# A.net
KiCad netlist of a schematic drawn in EAGLE
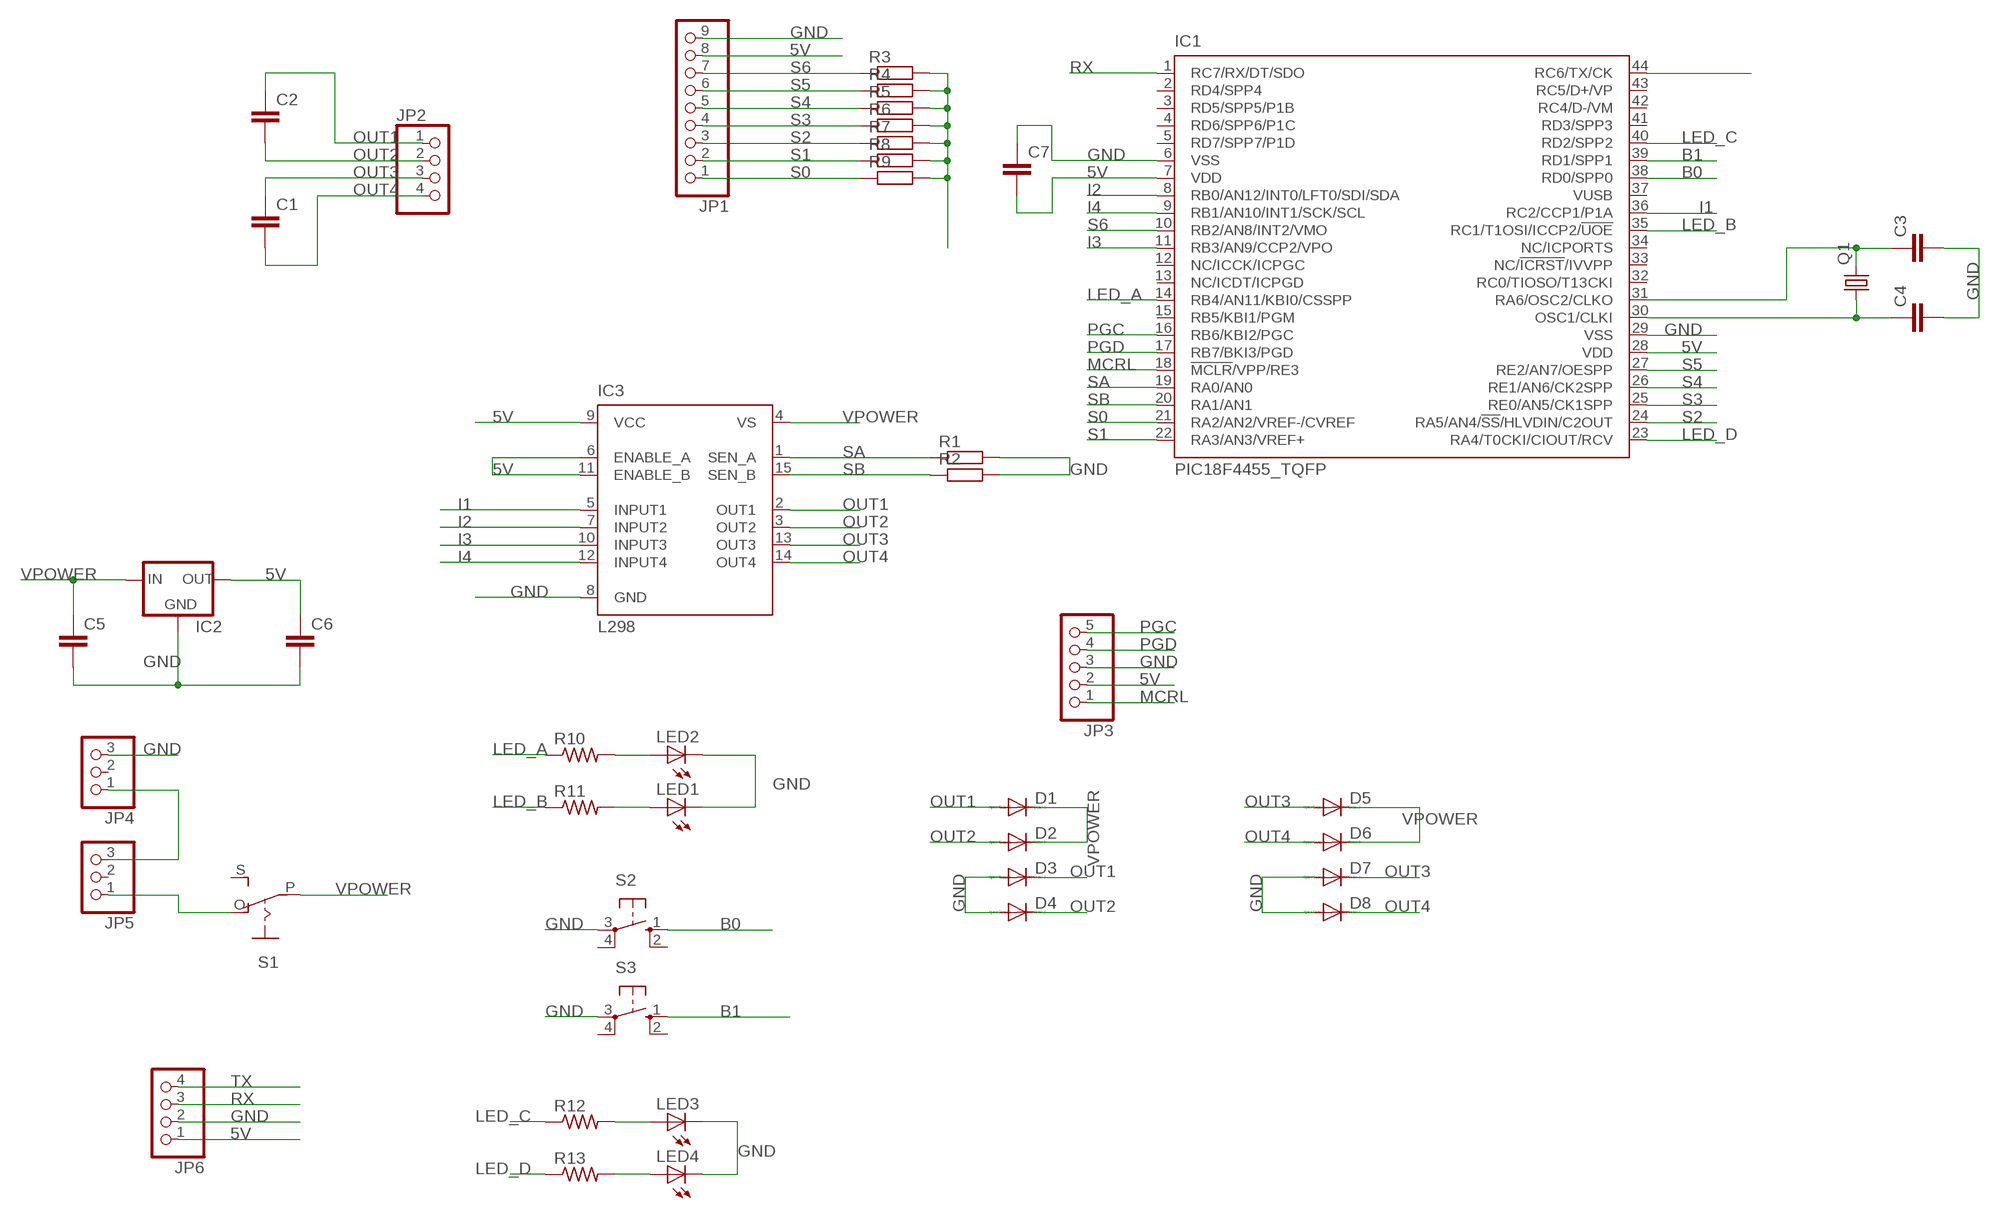
[diagram p0: schematic, sheet 1]

(export (version "E")
  (design (tool "Eeschema 10.0.6"))
  (components
    (comp (ref "C1")
      (value "C2,5-3")
      (footprint "eagle-import:C2.5-3")
      (libsource (lib "eagle-import") (part "C2,5-3"))
    )
    (comp (ref "C2")
      (value "C2,5-3")
      (footprint "eagle-import:C2.5-3")
      (libsource (lib "eagle-import") (part "C2,5-3"))
    )
    (comp (ref "C3")
      (value "C2,5-3")
      (footprint "eagle-import:C2.5-3")
      (libsource (lib "eagle-import") (part "C2,5-3"))
    )
    (comp (ref "C4")
      (value "C2,5-3")
      (footprint "eagle-import:C2.5-3")
      (libsource (lib "eagle-import") (part "C2,5-3"))
    )
    (comp (ref "C5")
      (value "C2,5-3")
      (footprint "eagle-import:C2.5-3")
      (libsource (lib "eagle-import") (part "C2,5-3"))
    )
    (comp (ref "C6")
      (value "C2,5-3")
      (footprint "eagle-import:C2.5-3")
      (libsource (lib "eagle-import") (part "C2,5-3"))
    )
    (comp (ref "C7")
      (value "C2,5-3")
      (footprint "eagle-import:C2.5-3")
      (libsource (lib "eagle-import") (part "C2,5-3"))
    )
    (comp (ref "D1")
      (value "DIODE-DO214AC")
      (footprint "eagle-import:DO214AC")
      (libsource (lib "eagle-import") (part "DIODE-DO214AC"))
    )
    (comp (ref "D2")
      (value "DIODE-DO214AC")
      (footprint "eagle-import:DO214AC")
      (libsource (lib "eagle-import") (part "DIODE-DO214AC"))
    )
    (comp (ref "D3")
      (value "DIODE-DO214AC")
      (footprint "eagle-import:DO214AC")
      (libsource (lib "eagle-import") (part "DIODE-DO214AC"))
    )
    (comp (ref "D4")
      (value "DIODE-DO214AC")
      (footprint "eagle-import:DO214AC")
      (libsource (lib "eagle-import") (part "DIODE-DO214AC"))
    )
    (comp (ref "D5")
      (value "DIODE-DO214AC")
      (footprint "eagle-import:DO214AC")
      (libsource (lib "eagle-import") (part "DIODE-DO214AC"))
    )
    (comp (ref "D6")
      (value "DIODE-DO214AC")
      (footprint "eagle-import:DO214AC")
      (libsource (lib "eagle-import") (part "DIODE-DO214AC"))
    )
    (comp (ref "D7")
      (value "DIODE-DO214AC")
      (footprint "eagle-import:DO214AC")
      (libsource (lib "eagle-import") (part "DIODE-DO214AC"))
    )
    (comp (ref "D8")
      (value "DIODE-DO214AC")
      (footprint "eagle-import:DO214AC")
      (libsource (lib "eagle-import") (part "DIODE-DO214AC"))
    )
    (comp (ref "IC1")
      (value "PIC18F4455_TQFP")
      (footprint "eagle-import:TQFP44")
      (fields (field (name "MF") "MICROCHIP") (field (name "MPN") "PIC18F4455-I/PT"))
      (libsource (lib "eagle-import") (part "PIC18F4_TQFP455"))
    )
    (comp (ref "IC2")
      (value "78XXS")
      (footprint "eagle-import:78XXS")
      (libsource (lib "eagle-import") (part "78XXS"))
    )
    (comp (ref "IC3")
      (value "L298")
      (footprint "eagle-import:MULTIWATT-15")
      (fields (field (name "MPN") "L298N"))
      (libsource (lib "eagle-import") (part "L298"))
    )
    (comp (ref "JP1")
      (value "PINHD-1X9")
      (footprint "eagle-import:1X09")
      (libsource (lib "eagle-import") (part "PINHD-1X9"))
    )
    (comp (ref "JP2")
      (value "PINHD-1X4")
      (footprint "eagle-import:1X04")
      (libsource (lib "eagle-import") (part "PINHD-1X4"))
    )
    (comp (ref "JP3")
      (value "PINHD-1X5")
      (footprint "eagle-import:1X05")
      (libsource (lib "eagle-import") (part "PINHD-1X5"))
    )
    (comp (ref "JP4")
      (value "PINHD-1X3")
      (footprint "eagle-import:1X03")
      (libsource (lib "eagle-import") (part "PINHD-1X3"))
    )
    (comp (ref "JP5")
      (value "PINHD-1X3")
      (footprint "eagle-import:1X03")
      (libsource (lib "eagle-import") (part "PINHD-1X3"))
    )
    (comp (ref "JP6")
      (value "PINHD-1X4")
      (footprint "eagle-import:1X04")
      (libsource (lib "eagle-import") (part "PINHD-1X4"))
    )
    (comp (ref "LED1")
      (value "LEDCHIPLED_1206")
      (footprint "eagle-import:CHIPLED_1206")
      (libsource (lib "eagle-import") (part "LEDCHIPLED_1206"))
    )
    (comp (ref "LED2")
      (value "LEDCHIPLED_1206")
      (footprint "eagle-import:CHIPLED_1206")
      (libsource (lib "eagle-import") (part "LEDCHIPLED_1206"))
    )
    (comp (ref "LED3")
      (value "LEDCHIPLED_1206")
      (footprint "eagle-import:CHIPLED_1206")
      (libsource (lib "eagle-import") (part "LEDCHIPLED_1206"))
    )
    (comp (ref "LED4")
      (value "LEDCHIPLED_1206")
      (footprint "eagle-import:CHIPLED_1206")
      (libsource (lib "eagle-import") (part "LEDCHIPLED_1206"))
    )
    (comp (ref "Q1")
      (value "CRYSTALHC49S")
      (footprint "eagle-import:HC49_S")
      (libsource (lib "eagle-import") (part "CRYSTALHC49S"))
    )
    (comp (ref "R1")
      (value "R-EU_R2512")
      (footprint "eagle-import:R2512")
      (libsource (lib "eagle-import") (part "R-EU_R2512"))
    )
    (comp (ref "R2")
      (value "R-EU_R2512")
      (footprint "eagle-import:R2512")
      (libsource (lib "eagle-import") (part "R-EU_R2512"))
    )
    (comp (ref "R3")
      (value "R-EU_M0805")
      (footprint "eagle-import:M0805")
      (libsource (lib "eagle-import") (part "R-EU_M0805"))
    )
    (comp (ref "R4")
      (value "R-EU_M0805")
      (footprint "eagle-import:M0805")
      (libsource (lib "eagle-import") (part "R-EU_M0805"))
    )
    (comp (ref "R5")
      (value "R-EU_M0805")
      (footprint "eagle-import:M0805")
      (libsource (lib "eagle-import") (part "R-EU_M0805"))
    )
    (comp (ref "R6")
      (value "R-EU_M0805")
      (footprint "eagle-import:M0805")
      (libsource (lib "eagle-import") (part "R-EU_M0805"))
    )
    (comp (ref "R7")
      (value "R-EU_M0805")
      (footprint "eagle-import:M0805")
      (libsource (lib "eagle-import") (part "R-EU_M0805"))
    )
    (comp (ref "R8")
      (value "R-EU_M0805")
      (footprint "eagle-import:M0805")
      (libsource (lib "eagle-import") (part "R-EU_M0805"))
    )
    (comp (ref "R9")
      (value "R-EU_M0805")
      (footprint "eagle-import:M0805")
      (libsource (lib "eagle-import") (part "R-EU_M0805"))
    )
    (comp (ref "R10")
      (value "R-US_M0805")
      (footprint "eagle-import:M0805")
      (libsource (lib "eagle-import") (part "R-US_M0805"))
    )
    (comp (ref "R11")
      (value "R-US_M0805")
      (footprint "eagle-import:M0805")
      (libsource (lib "eagle-import") (part "R-US_M0805"))
    )
    (comp (ref "R12")
      (value "R-US_R0805")
      (footprint "eagle-import:R0805")
      (libsource (lib "eagle-import") (part "resistor_R-US_R0805"))
    )
    (comp (ref "R13")
      (value "R-US_R0805")
      (footprint "eagle-import:R0805")
      (libsource (lib "eagle-import") (part "resistor_R-US_R0805"))
    )
    (comp (ref "S1")
      (value "EG1218S")
      (footprint "eagle-import:EG1218")
      (libsource (lib "eagle-import") (part "EG1218S"))
    )
    (comp (ref "S2")
      (value "10-XX")
      (footprint "eagle-import:B3F-10XX")
      (fields (field (name "MPN") "B3F-1000"))
      (libsource (lib "eagle-import") (part "10-XX"))
    )
    (comp (ref "S3")
      (value "10-XX")
      (footprint "eagle-import:B3F-10XX")
      (fields (field (name "MPN") "B3F-1000"))
      (libsource (lib "eagle-import") (part "10-XX"))
    )
  )
  (nets
    (net (code "1") (name "/5V") (class "Default")
      (node (ref "C6") (pin "1") (pinfunction "1_1") (pintype "passive"))
      (node (ref "C7") (pin "2") (pinfunction "2_2") (pintype "passive"))
      (node (ref "IC1") (pin "28") (pinfunction "VDD_28") (pintype "power_in"))
      (node (ref "IC1") (pin "7") (pinfunction "VDD_7") (pintype "power_in"))
      (node (ref "IC2") (pin "OUT") (pinfunction "OUT_OUT") (pintype "passive"))
      (node (ref "IC3") (pin "11") (pinfunction "ENABLE_B_11") (pintype "input"))
      (node (ref "IC3") (pin "6") (pinfunction "ENABLE_A_6") (pintype "input"))
      (node (ref "IC3") (pin "9") (pinfunction "VCC_9") (pintype "power_in"))
      (node (ref "JP1") (pin "8") (pinfunction "8_8") (pintype "passive"))
      (node (ref "JP3") (pin "2") (pinfunction "2_2") (pintype "passive"))
      (node (ref "JP6") (pin "1") (pinfunction "1_1") (pintype "passive"))
      (node (ref "R3") (pin "2") (pinfunction "2_2") (pintype "passive"))
      (node (ref "R4") (pin "2") (pinfunction "2_2") (pintype "passive"))
      (node (ref "R5") (pin "2") (pinfunction "2_2") (pintype "passive"))
      (node (ref "R6") (pin "2") (pinfunction "2_2") (pintype "passive"))
      (node (ref "R7") (pin "2") (pinfunction "2_2") (pintype "passive"))
      (node (ref "R8") (pin "2") (pinfunction "2_2") (pintype "passive"))
      (node (ref "R9") (pin "2") (pinfunction "2_2") (pintype "passive"))
    )
    (net (code "2") (name "/B0") (class "Default")
      (node (ref "IC1") (pin "38") (pinfunction "RD0/SPP0_38") (pintype "bidirectional"))
      (node (ref "S2") (pin "1") (pinfunction "S_1") (pintype "passive"))
    )
    (net (code "3") (name "/B1") (class "Default")
      (node (ref "IC1") (pin "39") (pinfunction "RD1/SPP1_39") (pintype "bidirectional"))
      (node (ref "S3") (pin "1") (pinfunction "S_1") (pintype "passive"))
    )
    (net (code "4") (name "/GND") (class "Default")
      (node (ref "C3") (pin "2") (pinfunction "2_2") (pintype "passive"))
      (node (ref "C4") (pin "2") (pinfunction "2_2") (pintype "passive"))
      (node (ref "C5") (pin "2") (pinfunction "2_2") (pintype "passive"))
      (node (ref "C6") (pin "2") (pinfunction "2_2") (pintype "passive"))
      (node (ref "C7") (pin "1") (pinfunction "1_1") (pintype "passive"))
      (node (ref "D3") (pin "A") (pinfunction "A_A") (pintype "passive"))
      (node (ref "D4") (pin "A") (pinfunction "A_A") (pintype "passive"))
      (node (ref "D7") (pin "A") (pinfunction "A_A") (pintype "passive"))
      (node (ref "D8") (pin "A") (pinfunction "A_A") (pintype "passive"))
      (node (ref "IC1") (pin "29") (pinfunction "VSS_29") (pintype "power_in"))
      (node (ref "IC1") (pin "6") (pinfunction "VSS_6") (pintype "power_in"))
      (node (ref "IC2") (pin "GND") (pinfunction "GND_GND") (pintype "input"))
      (node (ref "IC3") (pin "8") (pinfunction "GND_8") (pintype "power_in"))
      (node (ref "JP1") (pin "9") (pinfunction "9_9") (pintype "passive"))
      (node (ref "JP3") (pin "3") (pinfunction "3_3") (pintype "passive"))
      (node (ref "JP4") (pin "3") (pinfunction "3_3") (pintype "passive"))
      (node (ref "JP6") (pin "2") (pinfunction "2_2") (pintype "passive"))
      (node (ref "LED1") (pin "C") (pinfunction "C_C") (pintype "passive"))
      (node (ref "LED2") (pin "C") (pinfunction "C_C") (pintype "passive"))
      (node (ref "LED3") (pin "C") (pinfunction "C_C") (pintype "passive"))
      (node (ref "LED4") (pin "C") (pinfunction "C_C") (pintype "passive"))
      (node (ref "R1") (pin "2") (pinfunction "2_2") (pintype "passive"))
      (node (ref "R2") (pin "2") (pinfunction "2_2") (pintype "passive"))
      (node (ref "S2") (pin "3") (pinfunction "P_3") (pintype "passive"))
      (node (ref "S3") (pin "3") (pinfunction "P_3") (pintype "passive"))
    )
    (net (code "5") (name "/I1") (class "Default")
      (node (ref "IC1") (pin "36") (pinfunction "RC2/CCP1/P1A_36") (pintype "bidirectional"))
      (node (ref "IC3") (pin "5") (pinfunction "INPUT1_5") (pintype "input"))
    )
    (net (code "6") (name "/I2") (class "Default")
      (node (ref "IC1") (pin "8") (pinfunction "RB0/AN12/INT0/LFT0/SDI/SDA_8") (pintype "bidirectional"))
      (node (ref "IC3") (pin "7") (pinfunction "INPUT2_7") (pintype "input"))
    )
    (net (code "7") (name "/I3") (class "Default")
      (node (ref "IC1") (pin "11") (pinfunction "RB3/AN9/CCP2/VPO_11") (pintype "bidirectional"))
      (node (ref "IC3") (pin "10") (pinfunction "INPUT3_10") (pintype "input"))
    )
    (net (code "8") (name "/I4") (class "Default")
      (node (ref "IC1") (pin "9") (pinfunction "RB1/AN10/INT1/SCK/SCL_9") (pintype "bidirectional"))
      (node (ref "IC3") (pin "12") (pinfunction "INPUT4_12") (pintype "input"))
    )
    (net (code "9") (name "/LED_A") (class "Default")
      (node (ref "IC1") (pin "14") (pinfunction "RB4/AN11/KBI0/CSSPP_14") (pintype "bidirectional"))
      (node (ref "R10") (pin "1") (pinfunction "1_1") (pintype "passive"))
    )
    (net (code "10") (name "/LED_B") (class "Default")
      (node (ref "IC1") (pin "35") (pinfunction "RC1/T1OSI/ICCP2/~{UOE}_35") (pintype "bidirectional"))
      (node (ref "R11") (pin "1") (pinfunction "1_1") (pintype "passive"))
    )
    (net (code "11") (name "/LED_C") (class "Default")
      (node (ref "IC1") (pin "40") (pinfunction "RD2/SPP2_40") (pintype "bidirectional"))
      (node (ref "R12") (pin "1") (pinfunction "1_1") (pintype "passive"))
    )
    (net (code "12") (name "/LED_D") (class "Default")
      (node (ref "IC1") (pin "23") (pinfunction "RA4/T0CKI/CIOUT/RCV_23") (pintype "bidirectional"))
      (node (ref "R13") (pin "1") (pinfunction "1_1") (pintype "passive"))
    )
    (net (code "13") (name "/MCRL") (class "Default")
      (node (ref "IC1") (pin "18") (pinfunction "~{MCLR}/VPP/RE3_18") (pintype "input"))
      (node (ref "JP3") (pin "1") (pinfunction "1_1") (pintype "passive"))
    )
    (net (code "14") (name "/OUT1") (class "Default")
      (node (ref "C2") (pin "1") (pinfunction "1_1") (pintype "passive"))
      (node (ref "D1") (pin "A") (pinfunction "A_A") (pintype "passive"))
      (node (ref "D3") (pin "C") (pinfunction "C_C") (pintype "passive"))
      (node (ref "IC3") (pin "2") (pinfunction "OUT1_2") (pintype "output"))
      (node (ref "JP2") (pin "1") (pinfunction "1_1") (pintype "passive"))
    )
    (net (code "15") (name "/OUT2") (class "Default")
      (node (ref "C2") (pin "2") (pinfunction "2_2") (pintype "passive"))
      (node (ref "D2") (pin "A") (pinfunction "A_A") (pintype "passive"))
      (node (ref "D4") (pin "C") (pinfunction "C_C") (pintype "passive"))
      (node (ref "IC3") (pin "3") (pinfunction "OUT2_3") (pintype "output"))
      (node (ref "JP2") (pin "2") (pinfunction "2_2") (pintype "passive"))
    )
    (net (code "16") (name "/OUT3") (class "Default")
      (node (ref "C1") (pin "1") (pinfunction "1_1") (pintype "passive"))
      (node (ref "D5") (pin "A") (pinfunction "A_A") (pintype "passive"))
      (node (ref "D7") (pin "C") (pinfunction "C_C") (pintype "passive"))
      (node (ref "IC3") (pin "13") (pinfunction "OUT3_13") (pintype "output"))
      (node (ref "JP2") (pin "3") (pinfunction "3_3") (pintype "passive"))
    )
    (net (code "17") (name "/OUT4") (class "Default")
      (node (ref "C1") (pin "2") (pinfunction "2_2") (pintype "passive"))
      (node (ref "D6") (pin "A") (pinfunction "A_A") (pintype "passive"))
      (node (ref "D8") (pin "C") (pinfunction "C_C") (pintype "passive"))
      (node (ref "IC3") (pin "14") (pinfunction "OUT4_14") (pintype "output"))
      (node (ref "JP2") (pin "4") (pinfunction "4_4") (pintype "passive"))
    )
    (net (code "18") (name "/PGC") (class "Default")
      (node (ref "IC1") (pin "16") (pinfunction "RB6/KBI2/PGC_16") (pintype "bidirectional"))
      (node (ref "JP3") (pin "5") (pinfunction "5_5") (pintype "passive"))
    )
    (net (code "19") (name "/PGD") (class "Default")
      (node (ref "IC1") (pin "17") (pinfunction "RB7/BKI3/PGD_17") (pintype "bidirectional"))
      (node (ref "JP3") (pin "4") (pinfunction "4_4") (pintype "passive"))
    )
    (net (code "20") (name "/RX") (class "Default")
      (node (ref "IC1") (pin "1") (pinfunction "RC7/RX/DT/SDO_1") (pintype "bidirectional"))
      (node (ref "JP6") (pin "3") (pinfunction "3_3") (pintype "passive"))
    )
    (net (code "21") (name "/S0") (class "Default")
      (node (ref "IC1") (pin "21") (pinfunction "RA2/AN2/VREF-/CVREF_21") (pintype "bidirectional"))
      (node (ref "JP1") (pin "1") (pinfunction "1_1") (pintype "passive"))
      (node (ref "R9") (pin "1") (pinfunction "1_1") (pintype "passive"))
    )
    (net (code "22") (name "/S1") (class "Default")
      (node (ref "IC1") (pin "22") (pinfunction "RA3/AN3/VREF+_22") (pintype "bidirectional"))
      (node (ref "JP1") (pin "2") (pinfunction "2_2") (pintype "passive"))
      (node (ref "R8") (pin "1") (pinfunction "1_1") (pintype "passive"))
    )
    (net (code "23") (name "/S2") (class "Default")
      (node (ref "IC1") (pin "24") (pinfunction "RA5/AN4/~{SS}/HLVDIN/C2OUT_24") (pintype "bidirectional"))
      (node (ref "JP1") (pin "3") (pinfunction "3_3") (pintype "passive"))
      (node (ref "R7") (pin "1") (pinfunction "1_1") (pintype "passive"))
    )
    (net (code "24") (name "/S3") (class "Default")
      (node (ref "IC1") (pin "25") (pinfunction "RE0/AN5/CK1SPP_25") (pintype "bidirectional"))
      (node (ref "JP1") (pin "4") (pinfunction "4_4") (pintype "passive"))
      (node (ref "R6") (pin "1") (pinfunction "1_1") (pintype "passive"))
    )
    (net (code "25") (name "/S4") (class "Default")
      (node (ref "IC1") (pin "26") (pinfunction "RE1/AN6/CK2SPP_26") (pintype "bidirectional"))
      (node (ref "JP1") (pin "5") (pinfunction "5_5") (pintype "passive"))
      (node (ref "R5") (pin "1") (pinfunction "1_1") (pintype "passive"))
    )
    (net (code "26") (name "/S5") (class "Default")
      (node (ref "IC1") (pin "27") (pinfunction "RE2/AN7/OESPP_27") (pintype "bidirectional"))
      (node (ref "JP1") (pin "6") (pinfunction "6_6") (pintype "passive"))
      (node (ref "R4") (pin "1") (pinfunction "1_1") (pintype "passive"))
    )
    (net (code "27") (name "/S6") (class "Default")
      (node (ref "IC1") (pin "10") (pinfunction "RB2/AN8/INT2/VMO_10") (pintype "bidirectional"))
      (node (ref "JP1") (pin "7") (pinfunction "7_7") (pintype "passive"))
      (node (ref "R3") (pin "1") (pinfunction "1_1") (pintype "passive"))
    )
    (net (code "28") (name "/SA") (class "Default")
      (node (ref "IC1") (pin "19") (pinfunction "RA0/AN0_19") (pintype "bidirectional"))
      (node (ref "IC3") (pin "1") (pinfunction "SEN_A_1") (pintype "input"))
      (node (ref "R1") (pin "1") (pinfunction "1_1") (pintype "passive"))
    )
    (net (code "29") (name "/SB") (class "Default")
      (node (ref "IC1") (pin "20") (pinfunction "RA1/AN1_20") (pintype "bidirectional"))
      (node (ref "IC3") (pin "15") (pinfunction "SEN_B_15") (pintype "input"))
      (node (ref "R2") (pin "1") (pinfunction "1_1") (pintype "passive"))
    )
    (net (code "30") (name "/TX") (class "Default")
      (node (ref "IC1") (pin "44") (pinfunction "RC6/TX/CK_44") (pintype "bidirectional"))
      (node (ref "JP6") (pin "4") (pinfunction "4_4") (pintype "passive"))
    )
    (net (code "31") (name "/VPOWER") (class "Default")
      (node (ref "C5") (pin "1") (pinfunction "1_1") (pintype "passive"))
      (node (ref "D1") (pin "C") (pinfunction "C_C") (pintype "passive"))
      (node (ref "D2") (pin "C") (pinfunction "C_C") (pintype "passive"))
      (node (ref "D5") (pin "C") (pinfunction "C_C") (pintype "passive"))
      (node (ref "D6") (pin "C") (pinfunction "C_C") (pintype "passive"))
      (node (ref "IC2") (pin "IN") (pinfunction "IN_IN") (pintype "input"))
      (node (ref "IC3") (pin "4") (pinfunction "VS_4") (pintype "power_in"))
      (node (ref "S1") (pin "P") (pinfunction "P_P") (pintype "passive"))
    )
    (net (code "32") (name "Net-(IC1-OSC1{slash}CLKI)") (class "Default")
      (node (ref "C4") (pin "1") (pinfunction "1_1") (pintype "passive"))
      (node (ref "IC1") (pin "30") (pinfunction "OSC1/CLKI_30") (pintype "input"))
      (node (ref "Q1") (pin "1") (pinfunction "1_1") (pintype "passive"))
    )
    (net (code "33") (name "Net-(IC1-RA6{slash}OSC2{slash}CLKO)") (class "Default")
      (node (ref "C3") (pin "1") (pinfunction "1_1") (pintype "passive"))
      (node (ref "IC1") (pin "31") (pinfunction "RA6/OSC2/CLKO_31") (pintype "output"))
      (node (ref "Q1") (pin "2") (pinfunction "2_2") (pintype "passive"))
    )
    (net (code "34") (name "Net-(JP4-Pad1)") (class "Default")
      (node (ref "JP4") (pin "1") (pinfunction "1_1") (pintype "passive"))
      (node (ref "JP5") (pin "3") (pinfunction "3_3") (pintype "passive"))
    )
    (net (code "35") (name "Net-(JP5-Pad1)") (class "Default")
      (node (ref "JP5") (pin "1") (pinfunction "1_1") (pintype "passive"))
      (node (ref "S1") (pin "O") (pinfunction "O_O") (pintype "passive"))
    )
    (net (code "36") (name "Net-(LED1-PadA)") (class "Default")
      (node (ref "LED1") (pin "A") (pinfunction "A_A") (pintype "passive"))
      (node (ref "R11") (pin "2") (pinfunction "2_2") (pintype "passive"))
    )
    (net (code "37") (name "Net-(LED2-PadA)") (class "Default")
      (node (ref "LED2") (pin "A") (pinfunction "A_A") (pintype "passive"))
      (node (ref "R10") (pin "2") (pinfunction "2_2") (pintype "passive"))
    )
    (net (code "38") (name "Net-(LED3-PadA)") (class "Default")
      (node (ref "LED3") (pin "A") (pinfunction "A_A") (pintype "passive"))
      (node (ref "R12") (pin "2") (pinfunction "2_2") (pintype "passive"))
    )
    (net (code "39") (name "Net-(LED4-PadA)") (class "Default")
      (node (ref "LED4") (pin "A") (pinfunction "A_A") (pintype "passive"))
      (node (ref "R13") (pin "2") (pinfunction "2_2") (pintype "passive"))
    )
    (net (code "40") (name "unconnected-(IC1-NC{slash}ICCK{slash}ICPGC-Pad12)") (class "Default")
      (node (ref "IC1") (pin "12") (pinfunction "NC/ICCK/ICPGC_12") (pintype "bidirectional"))
    )
    (net (code "41") (name "unconnected-(IC1-NC{slash}ICDT{slash}ICPGD-Pad13)") (class "Default")
      (node (ref "IC1") (pin "13") (pinfunction "NC/ICDT/ICPGD_13") (pintype "bidirectional"))
    )
    (net (code "42") (name "unconnected-(IC1-NC{slash}ICPORTS-Pad34)") (class "Default")
      (node (ref "IC1") (pin "34") (pinfunction "NC/ICPORTS_34") (pintype "input"))
    )
    (net (code "43") (name "unconnected-(IC1-NC{slash}~{ICRST}{slash}IVVPP-Pad33)") (class "Default")
      (node (ref "IC1") (pin "33") (pinfunction "NC/~{ICRST}/IVVPP_33") (pintype "input"))
    )
    (net (code "44") (name "unconnected-(IC1-RB5{slash}KBI1{slash}PGM-Pad15)") (class "Default")
      (node (ref "IC1") (pin "15") (pinfunction "RB5/KBI1/PGM_15") (pintype "bidirectional"))
    )
    (net (code "45") (name "unconnected-(IC1-RC0{slash}TIOSO{slash}T13CKI-Pad32)") (class "Default")
      (node (ref "IC1") (pin "32") (pinfunction "RC0/TIOSO/T13CKI_32") (pintype "bidirectional"))
    )
    (net (code "46") (name "unconnected-(IC1-RC4{slash}D-{slash}VM-Pad42)") (class "Default")
      (node (ref "IC1") (pin "42") (pinfunction "RC4/D-/VM_42") (pintype "bidirectional"))
    )
    (net (code "47") (name "unconnected-(IC1-RC5{slash}D+{slash}VP-Pad43)") (class "Default")
      (node (ref "IC1") (pin "43") (pinfunction "RC5/D+/VP_43") (pintype "bidirectional"))
    )
    (net (code "48") (name "unconnected-(IC1-RD3{slash}SPP3-Pad41)") (class "Default")
      (node (ref "IC1") (pin "41") (pinfunction "RD3/SPP3_41") (pintype "bidirectional"))
    )
    (net (code "49") (name "unconnected-(IC1-RD4{slash}SPP4-Pad2)") (class "Default")
      (node (ref "IC1") (pin "2") (pinfunction "RD4/SPP4_2") (pintype "bidirectional"))
    )
    (net (code "50") (name "unconnected-(IC1-RD5{slash}SPP5{slash}P1B-Pad3)") (class "Default")
      (node (ref "IC1") (pin "3") (pinfunction "RD5/SPP5/P1B_3") (pintype "bidirectional"))
    )
    (net (code "51") (name "unconnected-(IC1-RD6{slash}SPP6{slash}P1C-Pad4)") (class "Default")
      (node (ref "IC1") (pin "4") (pinfunction "RD6/SPP6/P1C_4") (pintype "bidirectional"))
    )
    (net (code "52") (name "unconnected-(IC1-RD7{slash}SPP7{slash}P1D-Pad5)") (class "Default")
      (node (ref "IC1") (pin "5") (pinfunction "RD7/SPP7/P1D_5") (pintype "bidirectional"))
    )
    (net (code "53") (name "unconnected-(IC1-VUSB-Pad37)") (class "Default")
      (node (ref "IC1") (pin "37") (pinfunction "VUSB_37") (pintype "bidirectional"))
    )
    (net (code "54") (name "unconnected-(JP4-Pad2)") (class "Default")
      (node (ref "JP4") (pin "2") (pinfunction "2_2") (pintype "passive"))
    )
    (net (code "55") (name "unconnected-(JP5-Pad2)") (class "Default")
      (node (ref "JP5") (pin "2") (pinfunction "2_2") (pintype "passive"))
    )
    (net (code "56") (name "unconnected-(S1-PadS)") (class "Default")
      (node (ref "S1") (pin "S") (pinfunction "S_S") (pintype "passive"))
    )
    (net (code "57") (name "unconnected-(S2-P1-Pad4)") (class "Default")
      (node (ref "S2") (pin "4") (pinfunction "P1_4") (pintype "passive"))
    )
    (net (code "58") (name "unconnected-(S2-S1-Pad2)") (class "Default")
      (node (ref "S2") (pin "2") (pinfunction "S1_2") (pintype "passive"))
    )
    (net (code "59") (name "unconnected-(S3-P1-Pad4)") (class "Default")
      (node (ref "S3") (pin "4") (pinfunction "P1_4") (pintype "passive"))
    )
    (net (code "60") (name "unconnected-(S3-S1-Pad2)") (class "Default")
      (node (ref "S3") (pin "2") (pinfunction "S1_2") (pintype "passive"))
    )
  )
)
